# Boost_regulator.net
KiCad netlist of a schematic drawn in Altium Designer
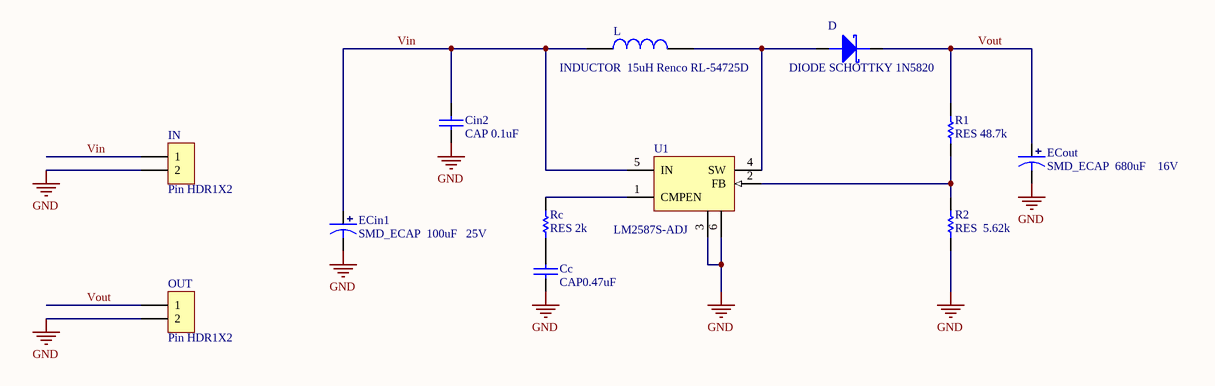
[diagram p0: Boost_regulator.SchDoc]

(export (version "E")
  (design (tool "Eeschema 10.0.6"))
  (components
    (comp (ref "Cc")
      (value "CAP0.47uF")
      (footprint "0805C")
      (description "无极性电容")
      (libsource (lib "电容") (part "CAP"))
    )
    (comp (ref "Cin2")
      (value "CAP 0.1uF")
      (footprint "0805C")
      (description "无极性电容")
      (libsource (lib "电容") (part "CAP"))
    )
    (comp (ref "D")
      (value "DIODE SCHOTTKY 1N5820")
      (footprint "SMA/DO-214AC")
      (description "肖特基二极管")
      (libsource (lib "二极管") (part "DIODE SCHOTTKY"))
    )
    (comp (ref "ECin1")
      (value "SMD_ECAP  100uF   25V")
      (footprint "SMD-EC8X8X10")
      (description "贴片电解电容")
      (libsource (lib "电容") (part "SMD_ECAP"))
    )
    (comp (ref "ECout")
      (value "SMD_ECAP  680uF    16V")
      (footprint "SMD-EC8X8X10")
      (description "贴片电解电容")
      (libsource (lib "电容") (part "SMD_ECAP"))
    )
    (comp (ref "IN")
      (value "Pin HDR1X2")
      (footprint "Pin HDR1X2/2.54mm-S")
      (libsource (lib "排针") (part "Pin HDR1X2"))
    )
    (comp (ref "L")
      (value "INDUCTOR  15uH Renco RL-54725D")
      (footprint "CDRH127")
      (description "INDUCTOR")
      (libsource (lib "电感") (part "INDUCTOR"))
    )
    (comp (ref "OUT")
      (value "Pin HDR1X2")
      (footprint "Pin HDR1X2/2.54mm-S")
      (libsource (lib "排针") (part "Pin HDR1X2"))
    )
    (comp (ref "R1") (value "RES 48.7k") (footprint "0603R") (libsource (lib "电阻") (part "RES")))
    (comp (ref "R2") (value "RES  5.62k") (footprint "0603R") (libsource (lib "电阻") (part "RES")))
    (comp (ref "Rc") (value "RES 2k") (footprint "0603R") (libsource (lib "电阻") (part "RES")))
    (comp (ref "U1")
      (value "LM2587S-ADJ")
      (footprint "TO-263-5")
      (description "DC升压")
      (fields (field (name "PUBLISHER") "Altium Limited"))
      (libsource (lib "fszhang") (part "LM2577S-ADJ"))
    )
  )
  (nets
    (net (code "1") (name "/Vin") (class "Default")
      (node (ref "Cin2") (pin "2") (pinfunction "2_2") (pintype "passive"))
      (node (ref "ECin1") (pin "1") (pinfunction "1_1") (pintype "passive"))
      (node (ref "IN") (pin "1") (pinfunction "1_1") (pintype "passive"))
      (node (ref "L") (pin "1") (pinfunction "1_1") (pintype "passive"))
      (node (ref "U1") (pin "5") (pinfunction "IN_5") (pintype "power_in"))
    )
    (net (code "2") (name "/Vout") (class "Default")
      (node (ref "D") (pin "K") (pinfunction "K_K") (pintype "passive"))
      (node (ref "ECout") (pin "1") (pinfunction "1_1") (pintype "passive"))
      (node (ref "OUT") (pin "1") (pinfunction "1_1") (pintype "passive"))
      (node (ref "R1") (pin "2") (pinfunction "2_2") (pintype "passive"))
    )
    (net (code "3") (name "GND") (class "Default")
      (node (ref "Cc") (pin "1") (pinfunction "1_1") (pintype "passive"))
      (node (ref "Cin2") (pin "1") (pinfunction "1_1") (pintype "passive"))
      (node (ref "ECin1") (pin "2") (pinfunction "2_2") (pintype "passive"))
      (node (ref "ECout") (pin "2") (pinfunction "2_2") (pintype "passive"))
      (node (ref "IN") (pin "2") (pinfunction "2_2") (pintype "passive"))
      (node (ref "OUT") (pin "2") (pinfunction "2_2") (pintype "passive"))
      (node (ref "R2") (pin "1") (pinfunction "1_1") (pintype "passive"))
      (node (ref "U1") (pin "3") (pinfunction "GND_3") (pintype "power_in"))
      (node (ref "U1") (pin "6") (pinfunction "6_6") (pintype "passive"))
    )
    (net (code "4") (name "Net-(Cc-Pad2)") (class "Default")
      (node (ref "Cc") (pin "2") (pinfunction "2_2") (pintype "passive"))
      (node (ref "Rc") (pin "1") (pinfunction "1_1") (pintype "passive"))
    )
    (net (code "5") (name "Net-(U1-CMPEN)") (class "Default")
      (node (ref "Rc") (pin "2") (pinfunction "2_2") (pintype "passive"))
      (node (ref "U1") (pin "1") (pinfunction "CMPEN_1") (pintype "passive"))
    )
    (net (code "6") (name "Net-(U1-FB)") (class "Default")
      (node (ref "R1") (pin "1") (pinfunction "1_1") (pintype "passive"))
      (node (ref "R2") (pin "2") (pinfunction "2_2") (pintype "passive"))
      (node (ref "U1") (pin "2") (pinfunction "FB_2") (pintype "input"))
    )
    (net (code "7") (name "Net-(U1-SW)") (class "Default")
      (node (ref "D") (pin "A") (pinfunction "A_A") (pintype "passive"))
      (node (ref "L") (pin "2") (pinfunction "2_2") (pintype "passive"))
      (node (ref "U1") (pin "4") (pinfunction "SW_4") (pintype "power_in"))
    )
  )
)
